# DIY_BalanceCar_2022-06-02.net
KiCad netlist of a schematic drawn in Altium Designer
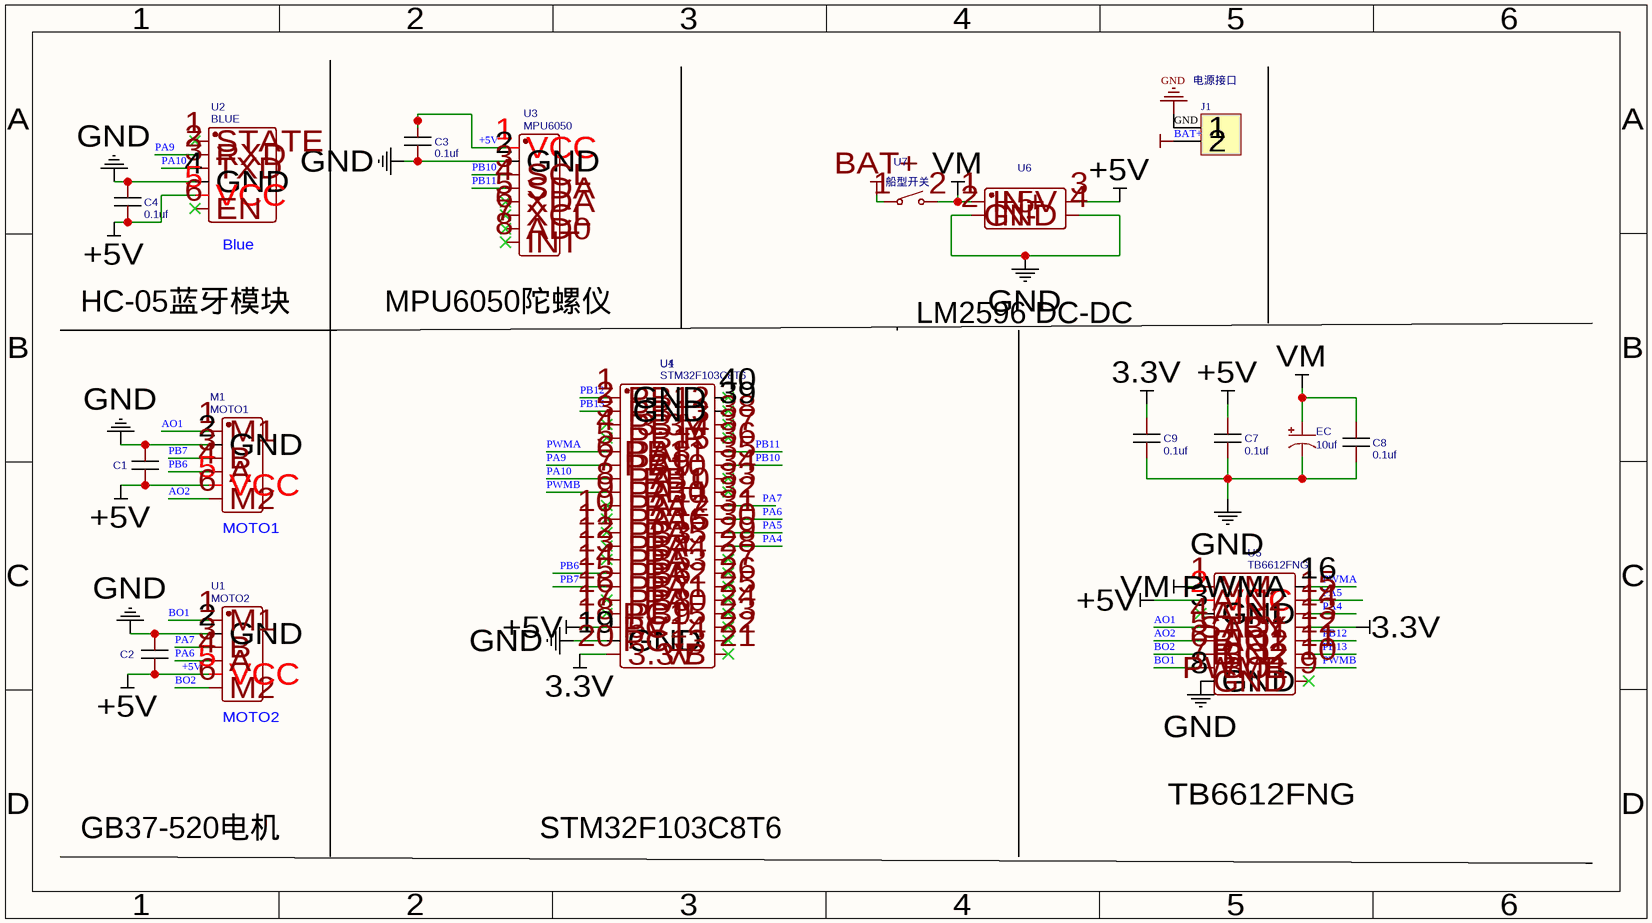
[diagram p0: DIY_BalanceCar_2022-06-02.schdoc]

(export (version "E")
  (design (tool "Eeschema 10.0.6"))
  (components
    (comp (ref "C1")
      (value "0.1uf")
      (fields
        (field (name "BOM_MANUFACTURER PART") "0.1uF 50V 4*5 Black high frequency")
        (field (name "BOM_SUPPLIER PART") "C45093")
        (field (name "CONTRIBUTOR") "heiweilu")
      )
      (libsource (lib "altium-import") (part "root_0_0.1uf_"))
    )
    (comp (ref "C2")
      (value "0.1uf")
      (fields
        (field (name "BOM_MANUFACTURER PART") "0.1uF 50V 4*5 Black high frequency")
        (field (name "BOM_SUPPLIER PART") "C45093")
        (field (name "CONTRIBUTOR") "heiweilu")
      )
      (libsource (lib "altium-import") (part "root_0_0.1uf_"))
    )
    (comp (ref "C3")
      (value "0.1uf")
      (fields (field (name "CONTRIBUTOR") "heiweilu"))
      (libsource (lib "altium-import") (part "root_0_0.1uf_"))
    )
    (comp (ref "C4")
      (value "0.1uf")
      (fields (field (name "CONTRIBUTOR") "heiweilu"))
      (libsource (lib "altium-import") (part "root_0_0.1uf_"))
    )
    (comp (ref "C7")
      (value "0.1uf")
      (fields (field (name "CONTRIBUTOR") "heiweilu"))
      (libsource (lib "altium-import") (part "root_0_0.1uf_"))
    )
    (comp (ref "C8")
      (value "0.1uf")
      (fields (field (name "CONTRIBUTOR") "heiweilu"))
      (libsource (lib "altium-import") (part "root_0_0.1uf_"))
    )
    (comp (ref "C9")
      (value "0.1uf")
      (fields (field (name "CONTRIBUTOR") "heiweilu"))
      (libsource (lib "altium-import") (part "root_0_0.1uf_"))
    )
    (comp (ref "C12")
      (value "10uf")
      (fields (field (name "CONTRIBUTOR") "heiweilu"))
      (libsource (lib "altium-import") (part "root_0_10uf_"))
    )
    (comp (ref "J")
      (value "电源接口")
      (fields
        (field (name "BOM_MANUFACTURER PART") "WJ301V-5.0-2P")
        (field (name "BOM_SUPPLIER PART") "C8475")
        (field (name "CONTRIBUTOR") "heiweilu")
      )
      (libsource (lib "altium-import") (part "root_0_电源接口_"))
    )
    (comp (ref "M1")
      (value "MOTO1")
      (fields
        (field (name "BOM_MANUFACTURER PART") "XH-6AW")
        (field (name "BOM_SUPPLIER PART") "C8876")
        (field (name "CONTRIBUTOR") "heiweilu")
      )
      (libsource (lib "altium-import") (part "root_0_MOTO1_"))
    )
    (comp (ref "U1")
      (value "MOTO2")
      (fields
        (field (name "BOM_MANUFACTURER PART") "XH-6AW")
        (field (name "BOM_SUPPLIER PART") "C8876")
        (field (name "CONTRIBUTOR") "heiweilu")
      )
      (libsource (lib "altium-import") (part "root_0_MOTO2_"))
    )
    (comp (ref "U2")
      (value "BLUE")
      (fields (field (name "CONTRIBUTOR") "heiweilu"))
      (libsource (lib "altium-import") (part "root_0_BLUE_"))
    )
    (comp (ref "U3")
      (value "MPU6050")
      (fields (field (name "CONTRIBUTOR") "heiweilu"))
      (libsource (lib "altium-import") (part "root_0_MPU6050_"))
    )
    (comp (ref "U4")
      (value "STM32F103C8T6")
      (fields (field (name "CONTRIBUTOR") "heiweilu"))
      (libsource (lib "altium-import") (part "root_0_STM32F103C8T6_"))
    )
    (comp (ref "U5")
      (value "TB6612FNG")
      (fields (field (name "CONTRIBUTOR") "heiweilu"))
      (libsource (lib "altium-import") (part "root_0_TB6612FNG_"))
    )
    (comp (ref "U6")
      (value "LM2596 DC-DC")
      (fields (field (name "CONTRIBUTOR") "heiweilu"))
      (libsource (lib "altium-import") (part "root_0_LM2596 DC-DC_"))
    )
    (comp (ref "U7")
      (value "船型开关")
      (fields (field (name "CONTRIBUTOR") "heiweilu"))
      (libsource (lib "altium-import") (part "root_0_船型开关_"))
    )
  )
  (nets
    (net (code "1") (name "+5V") (class "Default")
      (node (ref "C1") (pin "2") (pinfunction "2_2") (pintype "passive"))
      (node (ref "C2") (pin "2") (pinfunction "2_2") (pintype "passive"))
      (node (ref "C3") (pin "1") (pinfunction "1_1") (pintype "passive"))
      (node (ref "C4") (pin "2") (pinfunction "2_2") (pintype "passive"))
      (node (ref "C7") (pin "1") (pinfunction "1_1") (pintype "passive"))
      (node (ref "M1") (pin "5") (pinfunction "VCC_5") (pintype "passive"))
      (node (ref "U1") (pin "5") (pinfunction "VCC_5") (pintype "passive"))
      (node (ref "U2") (pin "5") (pinfunction "VCC_5") (pintype "passive"))
      (node (ref "U3") (pin "1") (pinfunction "VCC_1") (pintype "passive"))
      (node (ref "U4") (pin "18") (pinfunction "5V_18") (pintype "passive"))
      (node (ref "U5") (pin "2") (pinfunction "VCC_2") (pintype "passive"))
      (node (ref "U6") (pin "3") (pinfunction "+5V_3") (pintype "passive"))
    )
    (net (code "2") (name "/AO1") (class "Default")
      (node (ref "M1") (pin "1") (pinfunction "M1_1") (pintype "passive"))
      (node (ref "U5") (pin "4") (pinfunction "AO1_4") (pintype "passive"))
    )
    (net (code "3") (name "/AO2") (class "Default")
      (node (ref "M1") (pin "6") (pinfunction "M2_6") (pintype "passive"))
      (node (ref "U5") (pin "5") (pinfunction "AO2_5") (pintype "passive"))
    )
    (net (code "4") (name "/BO1") (class "Default")
      (node (ref "U1") (pin "1") (pinfunction "M1_1") (pintype "passive"))
      (node (ref "U5") (pin "7") (pinfunction "BO1_7") (pintype "passive"))
    )
    (net (code "5") (name "/BO2") (class "Default")
      (node (ref "U1") (pin "6") (pinfunction "M2_6") (pintype "passive"))
      (node (ref "U5") (pin "6") (pinfunction "BO2_6") (pintype "passive"))
    )
    (net (code "6") (name "/PA4") (class "Default")
      (node (ref "U4") (pin "29") (pinfunction "PA4_29") (pintype "passive"))
      (node (ref "U5") (pin "14") (pinfunction "AIN1_14") (pintype "passive"))
    )
    (net (code "7") (name "/PA5") (class "Default")
      (node (ref "U4") (pin "30") (pinfunction "PA5_30") (pintype "passive"))
      (node (ref "U5") (pin "15") (pinfunction "AIN2_15") (pintype "passive"))
    )
    (net (code "8") (name "/PA6") (class "Default")
      (node (ref "U1") (pin "4") (pinfunction "A_4") (pintype "passive"))
      (node (ref "U4") (pin "31") (pinfunction "PA6_31") (pintype "passive"))
    )
    (net (code "9") (name "/PA7") (class "Default")
      (node (ref "U1") (pin "3") (pinfunction "B_3") (pintype "passive"))
      (node (ref "U4") (pin "32") (pinfunction "PA7_32") (pintype "passive"))
    )
    (net (code "10") (name "/PA9") (class "Default")
      (node (ref "U2") (pin "2") (pinfunction "RXD_2") (pintype "passive"))
      (node (ref "U4") (pin "6") (pinfunction "PA9_6") (pintype "passive"))
    )
    (net (code "11") (name "/PA10") (class "Default")
      (node (ref "U2") (pin "3") (pinfunction "TXD_3") (pintype "passive"))
      (node (ref "U4") (pin "7") (pinfunction "PA10_7") (pintype "passive"))
    )
    (net (code "12") (name "/PB6") (class "Default")
      (node (ref "M1") (pin "4") (pinfunction "A_4") (pintype "passive"))
      (node (ref "U4") (pin "14") (pinfunction "PB6_14") (pintype "passive"))
    )
    (net (code "13") (name "/PB7") (class "Default")
      (node (ref "M1") (pin "3") (pinfunction "B_3") (pintype "passive"))
      (node (ref "U4") (pin "15") (pinfunction "PB7_15") (pintype "passive"))
    )
    (net (code "14") (name "/PB10") (class "Default")
      (node (ref "U3") (pin "3") (pinfunction "SCL_3") (pintype "passive"))
      (node (ref "U4") (pin "35") (pinfunction "PB10_35") (pintype "passive"))
    )
    (net (code "15") (name "/PB11") (class "Default")
      (node (ref "U3") (pin "4") (pinfunction "SDA_4") (pintype "passive"))
      (node (ref "U4") (pin "36") (pinfunction "PB11_36") (pintype "passive"))
    )
    (net (code "16") (name "/PB12") (class "Default")
      (node (ref "U4") (pin "1") (pinfunction "PB12_1") (pintype "passive"))
      (node (ref "U5") (pin "12") (pinfunction "BIN1_12") (pintype "passive"))
    )
    (net (code "17") (name "/PB13") (class "Default")
      (node (ref "U4") (pin "2") (pinfunction "PB13_2") (pintype "passive"))
      (node (ref "U5") (pin "11") (pinfunction "BIN2_11") (pintype "passive"))
    )
    (net (code "18") (name "/PWMA") (class "Default")
      (node (ref "U4") (pin "5") (pinfunction "PA8_5") (pintype "passive"))
      (node (ref "U5") (pin "16") (pinfunction "PWMA_16") (pintype "passive"))
    )
    (net (code "19") (name "/PWMB") (class "Default")
      (node (ref "U4") (pin "8") (pinfunction "PA11_8") (pintype "passive"))
      (node (ref "U5") (pin "10") (pinfunction "PWMB_10") (pintype "passive"))
    )
    (net (code "20") (name "3.3V") (class "Default")
      (node (ref "C9") (pin "1") (pinfunction "1_1") (pintype "passive"))
      (node (ref "U4") (pin "20") (pinfunction "3.3V_20") (pintype "passive"))
      (node (ref "U5") (pin "13") (pinfunction "STBY_13") (pintype "passive"))
    )
    (net (code "21") (name "BAT+") (class "Default")
      (node (ref "J") (pin "2") (pinfunction "2_2") (pintype "passive"))
      (node (ref "U7") (pin "1") (pinfunction "1_1") (pintype "passive"))
    )
    (net (code "22") (name "GND") (class "Default")
      (node (ref "C1") (pin "1") (pinfunction "1_1") (pintype "passive"))
      (node (ref "C12") (pin "2") (pinfunction "2_2") (pintype "passive"))
      (node (ref "C2") (pin "1") (pinfunction "1_1") (pintype "passive"))
      (node (ref "C3") (pin "2") (pinfunction "2_2") (pintype "passive"))
      (node (ref "C4") (pin "1") (pinfunction "1_1") (pintype "passive"))
      (node (ref "C7") (pin "2") (pinfunction "2_2") (pintype "passive"))
      (node (ref "C8") (pin "2") (pinfunction "2_2") (pintype "passive"))
      (node (ref "C9") (pin "2") (pinfunction "2_2") (pintype "passive"))
      (node (ref "J") (pin "1") (pinfunction "1_1") (pintype "passive"))
      (node (ref "M1") (pin "2") (pinfunction "GND_2") (pintype "passive"))
      (node (ref "U1") (pin "2") (pinfunction "GND_2") (pintype "passive"))
      (node (ref "U2") (pin "4") (pinfunction "GND_4") (pintype "passive"))
      (node (ref "U3") (pin "2") (pinfunction "GND_2") (pintype "passive"))
      (node (ref "U4") (pin "19") (pinfunction "GND_19") (pintype "passive"))
      (node (ref "U5") (pin "8") (pinfunction "GND_8") (pintype "passive"))
      (node (ref "U6") (pin "2") (pinfunction "IN-_2") (pintype "passive"))
      (node (ref "U6") (pin "4") (pinfunction "GND_4") (pintype "passive"))
    )
    (net (code "23") (name "VM") (class "Default")
      (node (ref "C12") (pin "1") (pinfunction "1_1") (pintype "passive"))
      (node (ref "C8") (pin "1") (pinfunction "1_1") (pintype "passive"))
      (node (ref "U5") (pin "1") (pinfunction "VM_1") (pintype "passive"))
      (node (ref "U6") (pin "1") (pinfunction "IN+_1") (pintype "passive"))
      (node (ref "U7") (pin "2") (pinfunction "2_2") (pintype "passive"))
    )
    (net (code "24") (name "unconnected-(U2-EN-Pad6)") (class "Default")
      (node (ref "U2") (pin "6") (pinfunction "EN_6") (pintype "passive+no_connect"))
    )
    (net (code "25") (name "unconnected-(U2-STATE-Pad1)") (class "Default")
      (node (ref "U2") (pin "1") (pinfunction "STATE_1") (pintype "passive+no_connect"))
    )
    (net (code "26") (name "unconnected-(U3-AD0-Pad7)") (class "Default")
      (node (ref "U3") (pin "7") (pinfunction "AD0_7") (pintype "passive+no_connect"))
    )
    (net (code "27") (name "unconnected-(U3-INT-Pad8)") (class "Default")
      (node (ref "U3") (pin "8") (pinfunction "INT_8") (pintype "passive+no_connect"))
    )
    (net (code "28") (name "unconnected-(U3-XCL-Pad6)") (class "Default")
      (node (ref "U3") (pin "6") (pinfunction "XCL_6") (pintype "passive+no_connect"))
    )
    (net (code "29") (name "unconnected-(U3-XDA-Pad5)") (class "Default")
      (node (ref "U3") (pin "5") (pinfunction "XDA_5") (pintype "passive+no_connect"))
    )
    (net (code "30") (name "unconnected-(U4-3.3V-Pad38)") (class "Default")
      (node (ref "U4") (pin "38") (pinfunction "3.3V_38") (pintype "passive+no_connect"))
    )
    (net (code "31") (name "unconnected-(U4-GND-Pad39)") (class "Default")
      (node (ref "U4") (pin "39") (pinfunction "GND_39") (pintype "passive+no_connect"))
    )
    (net (code "32") (name "unconnected-(U4-GND-Pad40)") (class "Default")
      (node (ref "U4") (pin "40") (pinfunction "GND_40") (pintype "passive+no_connect"))
    )
    (net (code "33") (name "unconnected-(U4-PA0-Pad25)") (class "Default")
      (node (ref "U4") (pin "25") (pinfunction "PA0_25") (pintype "passive+no_connect"))
    )
    (net (code "34") (name "unconnected-(U4-PA1-Pad26)") (class "Default")
      (node (ref "U4") (pin "26") (pinfunction "PA1_26") (pintype "passive+no_connect"))
    )
    (net (code "35") (name "unconnected-(U4-PA2-Pad27)") (class "Default")
      (node (ref "U4") (pin "27") (pinfunction "PA2_27") (pintype "passive+no_connect"))
    )
    (net (code "36") (name "unconnected-(U4-PA3-Pad28)") (class "Default")
      (node (ref "U4") (pin "28") (pinfunction "PA3_28") (pintype "passive+no_connect"))
    )
    (net (code "37") (name "unconnected-(U4-PA12-Pad9)") (class "Default")
      (node (ref "U4") (pin "9") (pinfunction "PA12_9") (pintype "passive+no_connect"))
    )
    (net (code "38") (name "unconnected-(U4-PA15-Pad10)") (class "Default")
      (node (ref "U4") (pin "10") (pinfunction "PA15_10") (pintype "passive+no_connect"))
    )
    (net (code "39") (name "unconnected-(U4-PB0-Pad33)") (class "Default")
      (node (ref "U4") (pin "33") (pinfunction "PB0_33") (pintype "passive+no_connect"))
    )
    (net (code "40") (name "unconnected-(U4-PB1-Pad34)") (class "Default")
      (node (ref "U4") (pin "34") (pinfunction "PB1_34") (pintype "passive+no_connect"))
    )
    (net (code "41") (name "unconnected-(U4-PB3-Pad11)") (class "Default")
      (node (ref "U4") (pin "11") (pinfunction "PB3_11") (pintype "passive+no_connect"))
    )
    (net (code "42") (name "unconnected-(U4-PB4-Pad12)") (class "Default")
      (node (ref "U4") (pin "12") (pinfunction "PB4_12") (pintype "passive+no_connect"))
    )
    (net (code "43") (name "unconnected-(U4-PB5-Pad13)") (class "Default")
      (node (ref "U4") (pin "13") (pinfunction "PB5_13") (pintype "passive+no_connect"))
    )
    (net (code "44") (name "unconnected-(U4-PB8-Pad16)") (class "Default")
      (node (ref "U4") (pin "16") (pinfunction "PB8_16") (pintype "passive+no_connect"))
    )
    (net (code "45") (name "unconnected-(U4-PB9-Pad17)") (class "Default")
      (node (ref "U4") (pin "17") (pinfunction "PB9_17") (pintype "passive+no_connect"))
    )
    (net (code "46") (name "unconnected-(U4-PB14-Pad3)") (class "Default")
      (node (ref "U4") (pin "3") (pinfunction "PB14_3") (pintype "passive+no_connect"))
    )
    (net (code "47") (name "unconnected-(U4-PB15-Pad4)") (class "Default")
      (node (ref "U4") (pin "4") (pinfunction "PB15_4") (pintype "passive+no_connect"))
    )
    (net (code "48") (name "unconnected-(U4-PC13-Pad22)") (class "Default")
      (node (ref "U4") (pin "22") (pinfunction "PC13_22") (pintype "passive+no_connect"))
    )
    (net (code "49") (name "unconnected-(U4-PC14-Pad23)") (class "Default")
      (node (ref "U4") (pin "23") (pinfunction "PC14_23") (pintype "passive+no_connect"))
    )
    (net (code "50") (name "unconnected-(U4-PC15-Pad24)") (class "Default")
      (node (ref "U4") (pin "24") (pinfunction "PC15_24") (pintype "passive+no_connect"))
    )
    (net (code "51") (name "unconnected-(U4-R-Pad37)") (class "Default")
      (node (ref "U4") (pin "37") (pinfunction "R_37") (pintype "passive+no_connect"))
    )
    (net (code "52") (name "unconnected-(U4-VB-Pad21)") (class "Default")
      (node (ref "U4") (pin "21") (pinfunction "VB_21") (pintype "passive+no_connect"))
    )
    (net (code "53") (name "unconnected-(U5-GND-Pad3)") (class "Default")
      (node (ref "U5") (pin "3") (pinfunction "GND_3") (pintype "passive+no_connect"))
    )
    (net (code "54") (name "unconnected-(U5-GND-Pad9)") (class "Default")
      (node (ref "U5") (pin "9") (pinfunction "GND_9") (pintype "passive+no_connect"))
    )
  )
)
